# 10w_Driver.net
KiCad netlist of a schematic drawn in EAGLE
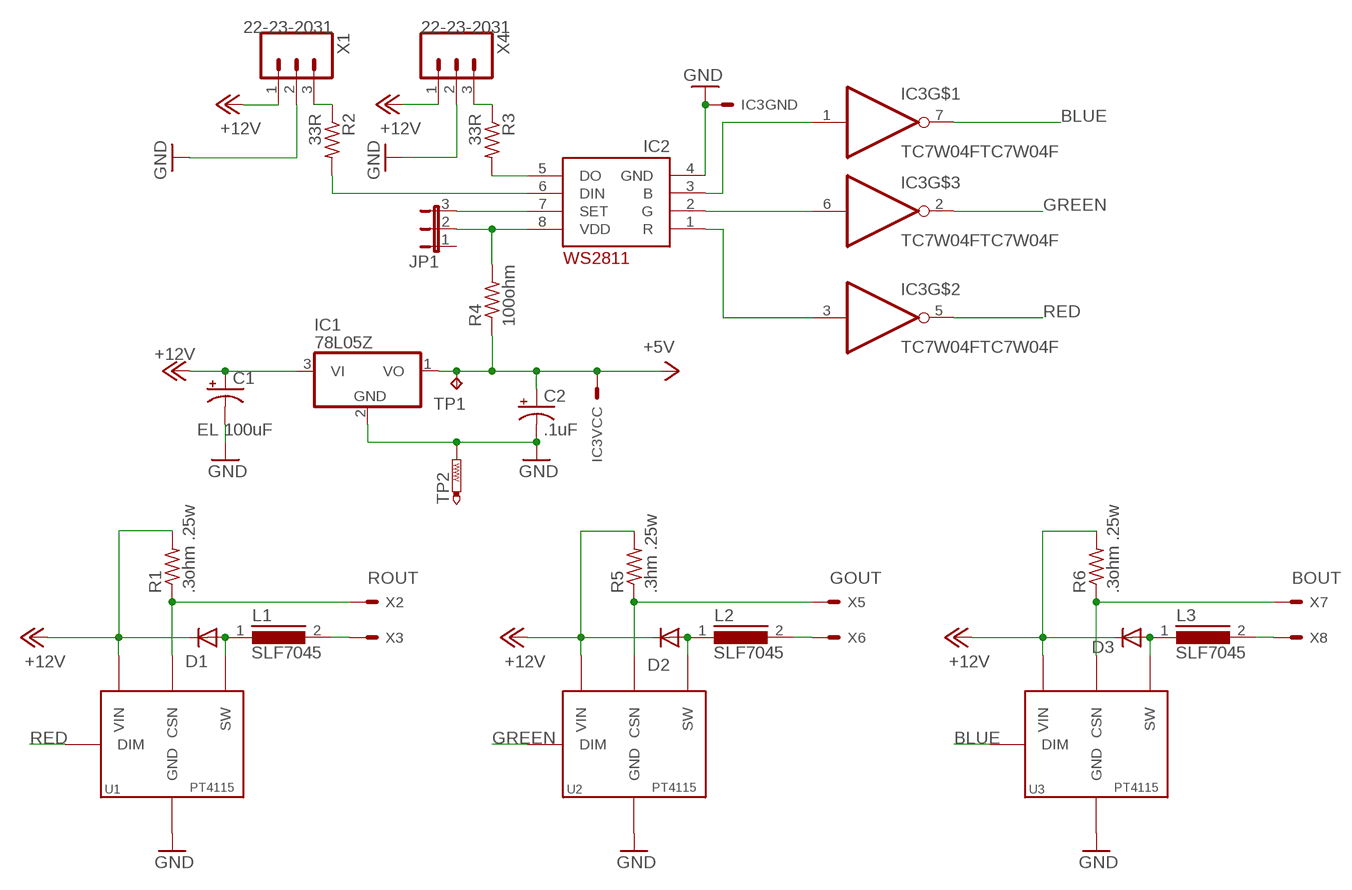
[diagram p0: schematic, sheet 1]

(export (version "E")
  (design (tool "Eeschema 10.0.6"))
  (components
    (comp (ref "C1")
      (value "EL 100uF")
      (footprint "eagle-import:TT2D6L")
      (libsource (lib "eagle-import") (part "CPOL-USTT2D6L"))
    )
    (comp (ref "C2")
      (value ".1uF")
      (footprint "eagle-import:B45181A")
      (libsource (lib "eagle-import") (part "resistor_CPOL-USB45181A"))
    )
    (comp (ref "D1")
      (value "DIODE-DO07")
      (footprint "eagle-import:DO07")
      (libsource (lib "eagle-import") (part "DIODE-DO07"))
    )
    (comp (ref "D2")
      (value "DIODE-DO07")
      (footprint "eagle-import:DO07")
      (libsource (lib "eagle-import") (part "DIODE-DO07"))
    )
    (comp (ref "D3")
      (value "DIODE-DO07")
      (footprint "eagle-import:DO07")
      (libsource (lib "eagle-import") (part "DIODE-DO07"))
    )
    (comp (ref "IC1")
      (value "78L05Z")
      (footprint "eagle-import:TO92")
      (libsource (lib "eagle-import") (part "78ZL05"))
    )
    (comp (ref "IC2")
      (value "WS2811-SOP8")
      (footprint "eagle-import:SO08-SKINNYPADS")
      (libsource (lib "eagle-import") (part "WS2811-SOP8"))
    )
    (comp (ref "IC3")
      (value "TC7W04FTC7W04F")
      (footprint "eagle-import:SO08")
      (libsource (lib "eagle-import") (part "TC7W04FTC7W04F"))
    )
    (comp (ref "JP1")
      (value "JP2E")
      (footprint "eagle-import:JP2")
      (libsource (lib "eagle-import") (part "JP2E"))
    )
    (comp (ref "L1")
      (value "SLF7045")
      (footprint "eagle-import:SLF7045")
      (libsource (lib "eagle-import") (part "SLF7045"))
    )
    (comp (ref "L2")
      (value "SLF7045")
      (footprint "eagle-import:SLF7045")
      (libsource (lib "eagle-import") (part "SLF7045"))
    )
    (comp (ref "L3")
      (value "SLF7045")
      (footprint "eagle-import:SLF7045")
      (libsource (lib "eagle-import") (part "SLF7045"))
    )
    (comp (ref "R1")
      (value ".3ohm .25w")
      (footprint "eagle-import:R1206")
      (libsource (lib "eagle-import") (part "resistor_R-US_R1206"))
    )
    (comp (ref "R2")
      (value "33R")
      (footprint "eagle-import:M0805")
      (libsource (lib "eagle-import") (part "R-US_M0805"))
    )
    (comp (ref "R3")
      (value "33R")
      (footprint "eagle-import:M0805")
      (libsource (lib "eagle-import") (part "R-US_M0805"))
    )
    (comp (ref "R4")
      (value "100ohm")
      (footprint "eagle-import:M0805")
      (libsource (lib "eagle-import") (part "R-US_M0805"))
    )
    (comp (ref "R5")
      (value ".3hm .25w")
      (footprint "eagle-import:M1206")
      (libsource (lib "eagle-import") (part "resistor_R-US_M1206"))
    )
    (comp (ref "R6")
      (value ".3ohm .25w")
      (footprint "eagle-import:R1206")
      (libsource (lib "eagle-import") (part "resistor_R-US_R1206"))
    )
    (comp (ref "TP1")
      (value "TPB2,54")
      (footprint "eagle-import:B2,54")
      (libsource (lib "eagle-import") (part "TPB2,54"))
    )
    (comp (ref "TP2")
      (value "PTR1TP20SQ")
      (footprint "eagle-import:TP20SQ")
      (libsource (lib "eagle-import") (part "PTR1TP20SQ"))
    )
    (comp (ref "U1")
      (value "PT4115PT4115B89E")
      (footprint "eagle-import:SOT89-5")
      (libsource (lib "eagle-import") (part "PT4115PT4115B89E"))
    )
    (comp (ref "U2")
      (value "PT4115PT4115B89E")
      (footprint "eagle-import:SOT89-5")
      (libsource (lib "eagle-import") (part "PT4115PT4115B89E"))
    )
    (comp (ref "U3")
      (value "PT4115PT4115B89E")
      (footprint "eagle-import:SOT89-5")
      (libsource (lib "eagle-import") (part "PT4115PT4115B89E"))
    )
    (comp (ref "X1")
      (value "22-23-2031")
      (footprint "eagle-import:22-23-2031")
      (fields (field (name "MF") "MOLEX"))
      (libsource (lib "eagle-import") (part "22-23-2031"))
    )
    (comp (ref "X2")
      (value "LED-PAD")
      (footprint "eagle-import:LED-PAD")
      (libsource (lib "eagle-import") (part "LED-PAD"))
    )
    (comp (ref "X3")
      (value "LED-PAD")
      (footprint "eagle-import:LED-PAD")
      (libsource (lib "eagle-import") (part "LED-PAD"))
    )
    (comp (ref "X4")
      (value "22-23-2031")
      (footprint "eagle-import:22-23-2031")
      (fields (field (name "MF") "MOLEX"))
      (libsource (lib "eagle-import") (part "22-23-2031"))
    )
    (comp (ref "X5")
      (value "LED-PAD")
      (footprint "eagle-import:LED-PAD")
      (libsource (lib "eagle-import") (part "LED-PAD"))
    )
    (comp (ref "X6")
      (value "LED-PAD")
      (footprint "eagle-import:LED-PAD")
      (libsource (lib "eagle-import") (part "LED-PAD"))
    )
    (comp (ref "X7")
      (value "LED-PAD")
      (footprint "eagle-import:LED-PAD")
      (libsource (lib "eagle-import") (part "LED-PAD"))
    )
    (comp (ref "X8")
      (value "LED-PAD")
      (footprint "eagle-import:LED-PAD")
      (libsource (lib "eagle-import") (part "LED-PAD"))
    )
  )
  (nets
    (net (code "1") (name "+5V") (class "Default")
      (node (ref "C2") (pin "+") (pinfunction "+_+") (pintype "passive"))
      (node (ref "IC1") (pin "1") (pinfunction "VO_1") (pintype "passive"))
      (node (ref "IC3") (pin "8") (pinfunction "S_8") (pintype "passive"))
      (node (ref "R4") (pin "1") (pinfunction "1_1") (pintype "passive"))
      (node (ref "TP1") (pin "TP") (pinfunction "TP_TP") (pintype "input"))
    )
    (net (code "2") (name "+12V") (class "Default")
      (node (ref "C1") (pin "+") (pinfunction "+_+") (pintype "passive"))
      (node (ref "D1") (pin "C") (pinfunction "C_C") (pintype "passive"))
      (node (ref "D2") (pin "C") (pinfunction "C_C") (pintype "passive"))
      (node (ref "D3") (pin "C") (pinfunction "C_C") (pintype "passive"))
      (node (ref "IC1") (pin "3") (pinfunction "VI_3") (pintype "input"))
      (node (ref "R1") (pin "2") (pinfunction "2_2") (pintype "passive"))
      (node (ref "R5") (pin "2") (pinfunction "2_2") (pintype "passive"))
      (node (ref "R6") (pin "2") (pinfunction "2_2") (pintype "passive"))
      (node (ref "U1") (pin "5") (pinfunction "VIN_5") (pintype "power_in"))
      (node (ref "U2") (pin "5") (pinfunction "VIN_5") (pintype "power_in"))
      (node (ref "U3") (pin "5") (pinfunction "VIN_5") (pintype "power_in"))
      (node (ref "X1") (pin "1") (pinfunction "1_1") (pintype "passive"))
      (node (ref "X4") (pin "1") (pinfunction "1_1") (pintype "passive"))
    )
    (net (code "3") (name "/BLUE") (class "Default")
      (node (ref "IC3") (pin "7") (pinfunction "O_7") (pintype "output"))
      (node (ref "U3") (pin "3") (pinfunction "DIM_3") (pintype "bidirectional"))
    )
    (net (code "4") (name "/BOUT") (class "Default")
      (node (ref "R6") (pin "1") (pinfunction "1_1") (pintype "passive"))
      (node (ref "U3") (pin "4") (pinfunction "CSN_4") (pintype "bidirectional"))
      (node (ref "X7") (pin "P$1@1") (pinfunction "S_P$1@1") (pintype "passive"))
      (node (ref "X7") (pin "P$1@2") (pinfunction "S_P$1@2") (pintype "passive"))
      (node (ref "X7") (pin "P$1@3") (pinfunction "S_P$1@3") (pintype "passive"))
    )
    (net (code "5") (name "/GOUT") (class "Default")
      (node (ref "R5") (pin "1") (pinfunction "1_1") (pintype "passive"))
      (node (ref "U2") (pin "4") (pinfunction "CSN_4") (pintype "bidirectional"))
      (node (ref "X5") (pin "P$1@1") (pinfunction "S_P$1@1") (pintype "passive"))
      (node (ref "X5") (pin "P$1@2") (pinfunction "S_P$1@2") (pintype "passive"))
      (node (ref "X5") (pin "P$1@3") (pinfunction "S_P$1@3") (pintype "passive"))
    )
    (net (code "6") (name "/GREEN") (class "Default")
      (node (ref "IC3") (pin "2") (pinfunction "O_2") (pintype "output"))
      (node (ref "U2") (pin "3") (pinfunction "DIM_3") (pintype "bidirectional"))
    )
    (net (code "7") (name "/RED") (class "Default")
      (node (ref "IC3") (pin "5") (pinfunction "O_5") (pintype "output"))
      (node (ref "U1") (pin "3") (pinfunction "DIM_3") (pintype "bidirectional"))
    )
    (net (code "8") (name "/ROUT") (class "Default")
      (node (ref "R1") (pin "1") (pinfunction "1_1") (pintype "passive"))
      (node (ref "U1") (pin "4") (pinfunction "CSN_4") (pintype "bidirectional"))
      (node (ref "X2") (pin "P$1@1") (pinfunction "S_P$1@1") (pintype "passive"))
      (node (ref "X2") (pin "P$1@2") (pinfunction "S_P$1@2") (pintype "passive"))
      (node (ref "X2") (pin "P$1@3") (pinfunction "S_P$1@3") (pintype "passive"))
    )
    (net (code "9") (name "GND") (class "Default")
      (node (ref "C1") (pin "-") (pinfunction "-_-") (pintype "passive"))
      (node (ref "C2") (pin "-") (pinfunction "-_-") (pintype "passive"))
      (node (ref "IC1") (pin "2") (pinfunction "GND_2") (pintype "passive"))
      (node (ref "IC2") (pin "4") (pinfunction "GND_4") (pintype "power_in"))
      (node (ref "IC3") (pin "4") (pinfunction "S_4") (pintype "passive"))
      (node (ref "TP2") (pin "TP") (pinfunction "TP_TP") (pintype "input"))
      (node (ref "U1") (pin "2") (pinfunction "GND_2") (pintype "power_in"))
      (node (ref "U1") (pin "2A") (pinfunction "GND_2A") (pintype "power_in"))
      (node (ref "U1") (pin "2A@1") (pinfunction "GND_2A@1") (pintype "power_in"))
      (node (ref "U1") (pin "2A@2") (pinfunction "GND_2A@2") (pintype "power_in"))
      (node (ref "U1") (pin "2A@3") (pinfunction "GND_2A@3") (pintype "power_in"))
      (node (ref "U1") (pin "2A@4") (pinfunction "GND_2A@4") (pintype "power_in"))
      (node (ref "U2") (pin "2") (pinfunction "GND_2") (pintype "power_in"))
      (node (ref "U2") (pin "2A") (pinfunction "GND_2A") (pintype "power_in"))
      (node (ref "U2") (pin "2A@1") (pinfunction "GND_2A@1") (pintype "power_in"))
      (node (ref "U2") (pin "2A@2") (pinfunction "GND_2A@2") (pintype "power_in"))
      (node (ref "U2") (pin "2A@3") (pinfunction "GND_2A@3") (pintype "power_in"))
      (node (ref "U2") (pin "2A@4") (pinfunction "GND_2A@4") (pintype "power_in"))
      (node (ref "U3") (pin "2") (pinfunction "GND_2") (pintype "power_in"))
      (node (ref "U3") (pin "2A") (pinfunction "GND_2A") (pintype "power_in"))
      (node (ref "U3") (pin "2A@1") (pinfunction "GND_2A@1") (pintype "power_in"))
      (node (ref "U3") (pin "2A@2") (pinfunction "GND_2A@2") (pintype "power_in"))
      (node (ref "U3") (pin "2A@3") (pinfunction "GND_2A@3") (pintype "power_in"))
      (node (ref "U3") (pin "2A@4") (pinfunction "GND_2A@4") (pintype "power_in"))
      (node (ref "X1") (pin "2") (pinfunction "2_2") (pintype "passive"))
      (node (ref "X4") (pin "2") (pinfunction "2_2") (pintype "passive"))
    )
    (net (code "10") (name "Net-(IC2-B)") (class "Default")
      (node (ref "IC2") (pin "3") (pinfunction "B_3") (pintype "open_collector"))
      (node (ref "IC3") (pin "1") (pinfunction "I_1") (pintype "input"))
    )
    (net (code "11") (name "Net-(IC2-DIN)") (class "Default")
      (node (ref "IC2") (pin "6") (pinfunction "DIN_6") (pintype "input"))
      (node (ref "R2") (pin "2") (pinfunction "2_2") (pintype "passive"))
    )
    (net (code "12") (name "Net-(IC2-DO)") (class "Default")
      (node (ref "IC2") (pin "5") (pinfunction "DO_5") (pintype "output"))
      (node (ref "R3") (pin "2") (pinfunction "2_2") (pintype "passive"))
    )
    (net (code "13") (name "Net-(IC2-G)") (class "Default")
      (node (ref "IC2") (pin "2") (pinfunction "G_2") (pintype "open_collector"))
      (node (ref "IC3") (pin "6") (pinfunction "I_6") (pintype "input"))
    )
    (net (code "14") (name "Net-(IC2-R)") (class "Default")
      (node (ref "IC2") (pin "1") (pinfunction "R_1") (pintype "open_collector"))
      (node (ref "IC3") (pin "3") (pinfunction "I_3") (pintype "input"))
    )
    (net (code "15") (name "Net-(IC2-SET)") (class "Default")
      (node (ref "IC2") (pin "7") (pinfunction "SET_7") (pintype "input"))
      (node (ref "JP1") (pin "3") (pinfunction "3_3") (pintype "passive"))
    )
    (net (code "16") (name "Net-(IC2-VDD)") (class "Default")
      (node (ref "IC2") (pin "8") (pinfunction "VDD_8") (pintype "power_in"))
      (node (ref "JP1") (pin "2") (pinfunction "2_2") (pintype "passive"))
      (node (ref "R4") (pin "2") (pinfunction "2_2") (pintype "passive"))
    )
    (net (code "17") (name "Net-(L1-Pad2)") (class "Default")
      (node (ref "L1") (pin "2") (pinfunction "2_2") (pintype "passive"))
      (node (ref "X3") (pin "P$1@1") (pinfunction "S_P$1@1") (pintype "passive"))
      (node (ref "X3") (pin "P$1@2") (pinfunction "S_P$1@2") (pintype "passive"))
      (node (ref "X3") (pin "P$1@3") (pinfunction "S_P$1@3") (pintype "passive"))
    )
    (net (code "18") (name "Net-(L2-Pad2)") (class "Default")
      (node (ref "L2") (pin "2") (pinfunction "2_2") (pintype "passive"))
      (node (ref "X6") (pin "P$1@1") (pinfunction "S_P$1@1") (pintype "passive"))
      (node (ref "X6") (pin "P$1@2") (pinfunction "S_P$1@2") (pintype "passive"))
      (node (ref "X6") (pin "P$1@3") (pinfunction "S_P$1@3") (pintype "passive"))
    )
    (net (code "19") (name "Net-(L3-Pad2)") (class "Default")
      (node (ref "L3") (pin "2") (pinfunction "2_2") (pintype "passive"))
      (node (ref "X8") (pin "P$1@1") (pinfunction "S_P$1@1") (pintype "passive"))
      (node (ref "X8") (pin "P$1@2") (pinfunction "S_P$1@2") (pintype "passive"))
      (node (ref "X8") (pin "P$1@3") (pinfunction "S_P$1@3") (pintype "passive"))
    )
    (net (code "20") (name "Net-(R2-Pad1)") (class "Default")
      (node (ref "R2") (pin "1") (pinfunction "1_1") (pintype "passive"))
      (node (ref "X1") (pin "3") (pinfunction "3_3") (pintype "passive"))
    )
    (net (code "21") (name "Net-(R3-Pad1)") (class "Default")
      (node (ref "R3") (pin "1") (pinfunction "1_1") (pintype "passive"))
      (node (ref "X4") (pin "3") (pinfunction "3_3") (pintype "passive"))
    )
    (net (code "22") (name "Net-(U1-SW)") (class "Default")
      (node (ref "D1") (pin "A") (pinfunction "A_A") (pintype "passive"))
      (node (ref "L1") (pin "1") (pinfunction "1_1") (pintype "passive"))
      (node (ref "U1") (pin "1") (pinfunction "SW_1") (pintype "bidirectional"))
    )
    (net (code "23") (name "Net-(U2-SW)") (class "Default")
      (node (ref "D2") (pin "A") (pinfunction "A_A") (pintype "passive"))
      (node (ref "L2") (pin "1") (pinfunction "1_1") (pintype "passive"))
      (node (ref "U2") (pin "1") (pinfunction "SW_1") (pintype "bidirectional"))
    )
    (net (code "24") (name "Net-(U3-SW)") (class "Default")
      (node (ref "D3") (pin "A") (pinfunction "A_A") (pintype "passive"))
      (node (ref "L3") (pin "1") (pinfunction "1_1") (pintype "passive"))
      (node (ref "U3") (pin "1") (pinfunction "SW_1") (pintype "bidirectional"))
    )
    (net (code "25") (name "unconnected-(JP1-Pad1)") (class "Default")
      (node (ref "JP1") (pin "1") (pinfunction "1_1") (pintype "passive"))
    )
  )
)
